# 02_56V-24V.net
KiCad netlist of a schematic drawn in Altium Designer
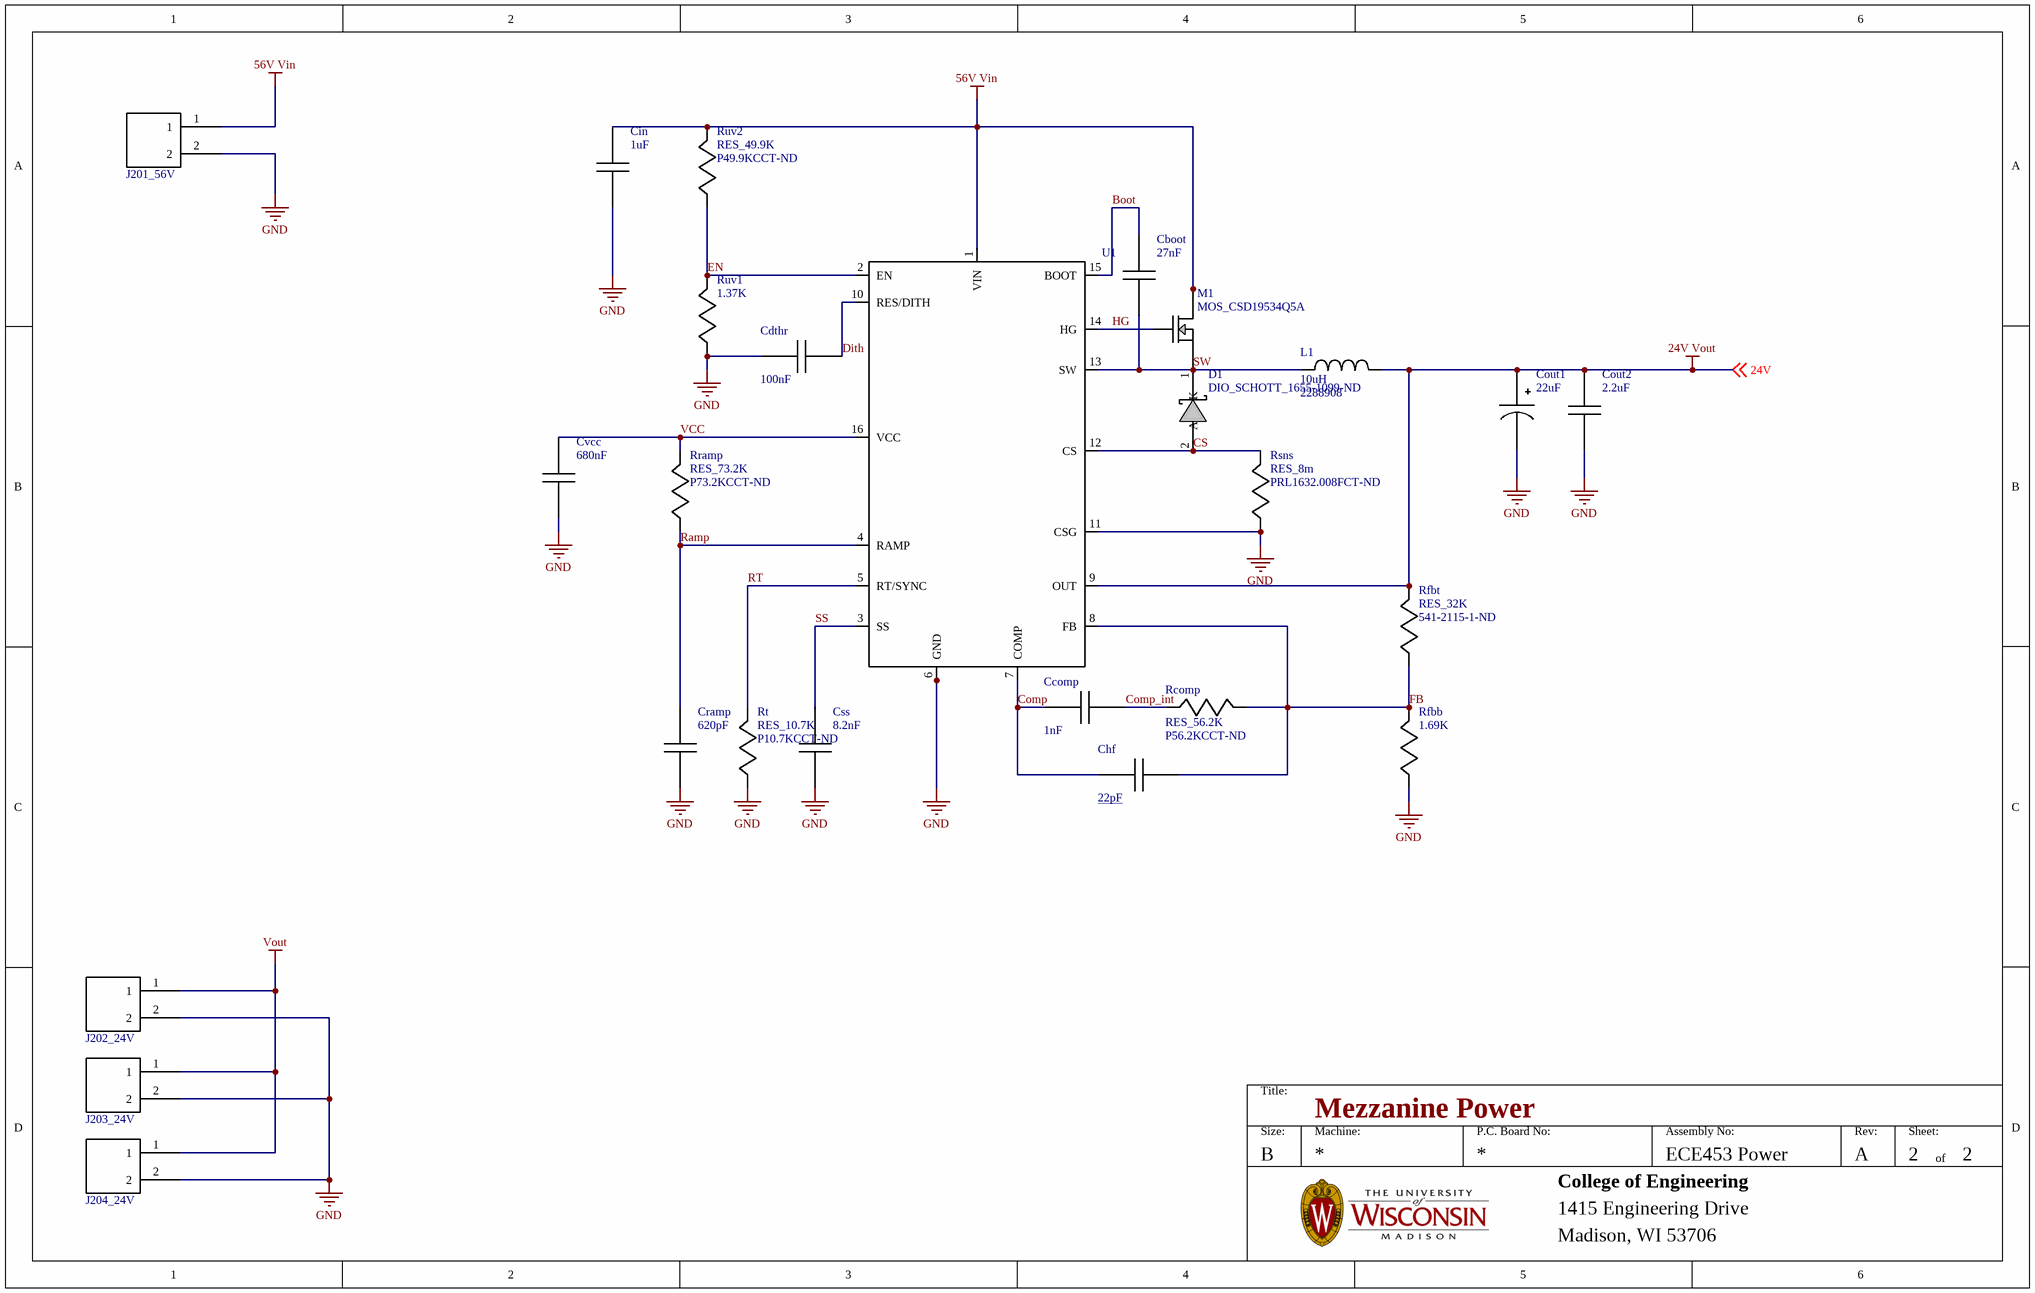
[diagram p0: 02 56V-24V.SchDoc]

(export (version "E")
  (design (tool "Eeschema 10.0.6"))
  (components
    (comp (ref "Cboot")
      (value "CAP_27nF")
      (footprint "CAP_1812")
      (description "Imported")
      (fields
        (field (name "MANUFACTURER_PART_NUMBER") "C1812C273J5GACTU")
        (field (name "MANUFACTURER") "KEMET")
        (field (name "CAPACITANCE") "27nF")
      )
      (libsource (lib "ECE453_PWR") (part "CAP_27nF"))
    )
    (comp (ref "Ccomp")
      (value "CAP_1nF")
      (footprint "CAP_0805")
      (description "Imported")
      (fields
        (field (name "MANUFACTURER_PART_NUMBER") "C0805C102K5GACTU")
        (field (name "MANUFACTURER") "KEMET")
        (field (name "CAPACITANCE") "1nF")
      )
      (libsource (lib "ECE453_PWR") (part "CAP_1nF"))
    )
    (comp (ref "Cdthr")
      (value "CAP_100nF")
      (footprint "CAP_0805")
      (description "Imported")
      (fields
        (field (name "MANUFACTURER_PART_NUMBER") "08053C104JAZ2A")
        (field (name "MANUFACTURER") "AVX Corporation")
        (field (name "CAPACITANCE") "100nF")
      )
      (libsource (lib "ECE453_PWR") (part "CAP_100nF"))
    )
    (comp (ref "Chf")
      (value "CAP_22pF")
      (footprint "CAP_0805")
      (description "Imported")
      (fields
        (field (name "MANUFACTURER_PART_NUMBER") "C0805C220K3GACTU")
        (field (name "MANUFACTURER") "KEMET")
        (field (name "CAPACITANCE") "22pF")
      )
      (libsource (lib "ECE453_PWR") (part "CAP_22pF"))
    )
    (comp (ref "Cin")
      (value "CAP_1uF")
      (footprint "CAP_1207")
      (description "Imported")
      (fields
        (field (name "MANUFACTURER_PART_NUMBER") "C3216X7R2A105K160AA")
        (field (name "MANUFACTURER") "TDK Corporation")
        (field (name "CAPACITANCE") "1uF")
      )
      (libsource (lib "ECE453_PWR") (part "CAP_1uF"))
    )
    (comp (ref "Cout1")
      (value "PCAP_22uF")
      (footprint "CAP_RAD_35SVPF22M")
      (description "Imported")
      (fields
        (field (name "MANUFACTURER_PART_NUMBER") "35SVPF22M")
        (field (name "MANUFACTURER") "Panasonic Electronic Components")
        (field (name "CAPACITANCE") "22uF")
      )
      (libsource (lib "ECE453_PWR") (part "PCAP_22uF"))
    )
    (comp (ref "Cout2")
      (value "CAP_2.2uF")
      (footprint "CAP_0805")
      (description "Imported")
      (fields
        (field (name "MANUFACTURER_PART_NUMBER") "C2012X7R1H225K125AC")
        (field (name "MANUFACTURER") "TDK Corporation")
        (field (name "CAPACITANCE") "2.2uF")
      )
      (libsource (lib "ECE453_PWR") (part "CAP_2.2uF"))
    )
    (comp (ref "Cramp")
      (value "CAP_620pF")
      (footprint "CAP_0805")
      (description "Imported")
      (fields
        (field (name "MANUFACTURER_PART_NUMBER") "CL21C621JBCNNNC")
        (field (name "MANUFACTURER") "Samsung Electro-Mechanics")
        (field (name "CAPACITANCE") "620pF")
      )
      (libsource (lib "ECE453_PWR") (part "CAP_620pF"))
    )
    (comp (ref "Css")
      (value "CAP_8.2nF")
      (footprint "CAP_0805")
      (description "Imported")
      (fields
        (field (name "MANUFACTURER") "Murata Electronics North America")
        (field (name "MANUFACTURER PART NUMBER") "GRM2195C1H822JA01D")
        (field (name "CAPACITANCE") "8.2nF")
      )
      (libsource (lib "ECE453_PWR") (part "CAP_8.2nF"))
    )
    (comp (ref "Cvcc")
      (value "CAP_680nF")
      (footprint "CAP_1207")
      (description "Imported")
      (fields
        (field (name "MANUFACTURER_PART_NUMBER") "ECPU1C684MA5")
        (field (name "MANUFACTURER") "Panasonic Electronic Components")
        (field (name "CAPACITANCE") "680nF")
      )
      (libsource (lib "ECE453_PWR") (part "CAP_680nF"))
    )
    (comp (ref "D1")
      (value "DIO_SCHOTT_1655-1099-ND")
      (footprint "DIO_SCHOTT_MBRF10200")
      (description "Imported")
      (fields
        (field (name "MANUFACTURER") "SMC Diode Solutions")
        (field (name "MANUFACTURER PART NUMBER") "MBRF10200")
      )
      (libsource (lib "ECE453_PWR") (part "DIO_SCHOTT_1655-1099-ND"))
    )
    (comp (ref "J201_56V")
      (value "TERMINAL_SCREW_2x1")
      (footprint "TERM_2Pin")
      (description "TERM BLOCK PLUG 2POS STR 5.08MM")
      (fields
        (field (name "MANUFACTURER") "On Shore Technology Inc.")
        (field (name "MANUFACTURER PART NUMBER") "OSTTJ025153")
      )
      (libsource (lib "ECE453_PWR") (part "TERMINAL_SCREW_2x1"))
    )
    (comp (ref "J202_24V")
      (value "TERMINAL_SCREW_2x1")
      (footprint "TERM_2Pin")
      (description "TERM BLOCK PLUG 2POS STR 5.08MM")
      (fields
        (field (name "MANUFACTURER") "On Shore Technology Inc.")
        (field (name "MANUFACTURER PART NUMBER") "OSTTJ025153")
      )
      (libsource (lib "ECE453_PWR") (part "TERMINAL_SCREW_2x1"))
    )
    (comp (ref "J203_24V")
      (value "TERMINAL_SCREW_2x1")
      (footprint "TERM_2Pin")
      (description "TERM BLOCK PLUG 2POS STR 5.08MM")
      (fields
        (field (name "MANUFACTURER") "On Shore Technology Inc.")
        (field (name "MANUFACTURER PART NUMBER") "OSTTJ025153")
      )
      (libsource (lib "ECE453_PWR") (part "TERMINAL_SCREW_2x1"))
    )
    (comp (ref "J204_24V")
      (value "TERMINAL_SCREW_2x1")
      (footprint "TERM_2Pin")
      (description "TERM BLOCK PLUG 2POS STR 5.08MM")
      (fields
        (field (name "MANUFACTURER") "On Shore Technology Inc.")
        (field (name "MANUFACTURER PART NUMBER") "OSTTJ025153")
      )
      (libsource (lib "ECE453_PWR") (part "TERMINAL_SCREW_2x1"))
    )
    (comp (ref "L1")
      (value "IND_10uH")
      (footprint "IND_SER2900")
      (description "Imported")
      (fields
        (field (name "MANUFACTURER_PART_NUMBER") "SER2915L-103KL")
        (field (name "MANUFACTURER") "COILCRAFT")
        (field (name "INDUCTANCE") "10uH")
        (field (name "SUPPLIER PART NUMBER 1") "2288908")
      )
      (libsource (lib "ECE453_PWR") (part "IND_10uH"))
    )
    (comp (ref "M1")
      (value "MOS_CSD19534Q5A")
      (footprint "MOS_CSD19534Q5A")
      (description "Imported")
      (fields
        (field (name "MANUFACTURER_PART_NUMBER") "CSD19534Q5A")
        (field (name "MANUFACTURER") "Texas Instruments")
      )
      (libsource (lib "ECE453_PWR") (part "MOS_CSD19534Q5A"))
    )
    (comp (ref "Rcomp")
      (value "RES_56.2K")
      (footprint "RES_0805")
      (description "Imported")
      (fields
        (field (name "MANUFACTURER_PART_NUMBER") "ERJ-6ENF5622V")
        (field (name "MANUFACTURER") "Panasonic Electronic Components")
        (field (name "SUPPLIER PART NUMBER 1") "P56.2KCCT-ND")
      )
      (libsource (lib "ECE453_PWR") (part "RES_56.2K"))
    )
    (comp (ref "Rfbb")
      (value "RES_1.69K")
      (footprint "RES_0805")
      (description "Imported")
      (fields
        (field (name "MANUFACTURER_PART_NUMBER") "ERJ-6ENF1691V")
        (field (name "MANUFACTURER") "Panasonic Electronic Components")
        (field (name "RESISTANCE") "1.69K")
      )
      (libsource (lib "ECE453_PWR") (part "RES_1.69K"))
    )
    (comp (ref "Rfbt")
      (value "RES_32K")
      (footprint "RES_0402")
      (description "Imported")
      (fields
        (field (name "MANUFACTURER") "Vishay Dale")
        (field (name "MANUFACTURER PART NUMBER") "TNPW040232K0BEED")
        (field (name "SUPPLIER PART NUMBER 1") "541-2115-1-ND")
      )
      (libsource (lib "ECE453_PWR") (part "RES_32K"))
    )
    (comp (ref "Rramp")
      (value "RES_73.2K")
      (footprint "RES_0805")
      (description "Imported")
      (fields
        (field (name "MANUFACTURER_PART_NUMBER") "ERJ-6ENF7322V")
        (field (name "MANUFACTURER") "Panasonic Electronic Components")
        (field (name "SUPPLIER PART NUMBER 1") "P73.2KCCT-ND")
      )
      (libsource (lib "ECE453_PWR") (part "RES_73.2K"))
    )
    (comp (ref "Rsns")
      (value "RES_8m")
      (footprint "RES_1206")
      (description "Imported")
      (fields
        (field (name "MANUFACTURER_PART_NUMBER") "PRL1632-R008-F-T1")
        (field (name "MANUFACTURER") "Susumu")
        (field (name "SUPPLIER PART NUMBER 1") "PRL1632.008FCT-ND")
      )
      (libsource (lib "ECE453_PWR") (part "RES_8m"))
    )
    (comp (ref "Rt")
      (value "RES_10.7K")
      (footprint "RES_0805")
      (description "Imported")
      (fields
        (field (name "MANUFACTURER_PART_NUMBER") "ERJ-6ENF1072V")
        (field (name "MANUFACTURER") "Panasonic Electronic Components")
        (field (name "SUPPLIER PART NUMBER 1") "P10.7KCCT-ND")
      )
      (libsource (lib "ECE453_PWR") (part "RES_10.7K"))
    )
    (comp (ref "Ruv1")
      (value "RES_1.37K")
      (footprint "RES_0805")
      (description "Imported")
      (fields
        (field (name "MANUFACTURER_PART_NUMBER") "CRCW08051K37FKEA")
        (field (name "MANUFACTURER") "Vishay Dale")
        (field (name "RESISTANCE") "1.37K")
      )
      (libsource (lib "ECE453_PWR") (part "RES_1.37K"))
    )
    (comp (ref "Ruv2")
      (value "RES_49.9K")
      (footprint "RES_0805")
      (description "Imported")
      (fields
        (field (name "MANUFACTURER_PART_NUMBER") "ERJ-6ENF4992V")
        (field (name "MANUFACTURER") "Panasonic Electronic Components")
        (field (name "SUPPLIER PART NUMBER 1") "P49.9KCCT-ND")
      )
      (libsource (lib "ECE453_PWR") (part "RES_49.9K"))
    )
    (comp (ref "U1")
      (value "BUCK_LM5088QMHX-1/NOP")
      (footprint "BUCK_LM5088")
      (description "Imported")
      (fields
        (field (name "MANUFACTURER_PART_NUMBER") "LM5088MHX-2/NOPB")
        (field (name "MANUFACTURER") "Texas Instruments")
      )
      (libsource (lib "ECE453_PWR") (part "BUCK_LM5088QMHX-1/NOP"))
    )
  )
  (nets
    (net (code "1") (name "/Boot") (class "Default")
      (node (ref "Cboot") (pin "1") (pinfunction "1_1") (pintype "passive"))
      (node (ref "U1") (pin "15") (pinfunction "BOOT_15") (pintype "passive"))
    )
    (net (code "2") (name "/CS") (class "Default")
      (node (ref "D1") (pin "2") (pinfunction "A_2") (pintype "passive"))
      (node (ref "Rsns") (pin "1") (pinfunction "1_1") (pintype "passive"))
      (node (ref "U1") (pin "12") (pinfunction "CS_12") (pintype "passive"))
    )
    (net (code "3") (name "/Comp") (class "Default")
      (node (ref "Ccomp") (pin "2") (pinfunction "2_2") (pintype "passive"))
      (node (ref "Chf") (pin "2") (pinfunction "2_2") (pintype "passive"))
      (node (ref "U1") (pin "7") (pinfunction "COMP_7") (pintype "passive"))
    )
    (net (code "4") (name "/Comp_int") (class "Default")
      (node (ref "Ccomp") (pin "1") (pinfunction "1_1") (pintype "passive"))
      (node (ref "Rcomp") (pin "2") (pinfunction "2_2") (pintype "passive"))
    )
    (net (code "5") (name "/Dith") (class "Default")
      (node (ref "Cdthr") (pin "1") (pinfunction "1_1") (pintype "passive"))
      (node (ref "U1") (pin "10") (pinfunction "RES/DITH_10") (pintype "passive"))
    )
    (net (code "6") (name "/EN") (class "Default")
      (node (ref "Ruv1") (pin "1") (pinfunction "1_1") (pintype "passive"))
      (node (ref "Ruv2") (pin "2") (pinfunction "2_2") (pintype "passive"))
      (node (ref "U1") (pin "2") (pinfunction "EN_2") (pintype "passive"))
    )
    (net (code "7") (name "/FB") (class "Default")
      (node (ref "Chf") (pin "1") (pinfunction "1_1") (pintype "passive"))
      (node (ref "Rcomp") (pin "1") (pinfunction "1_1") (pintype "passive"))
      (node (ref "Rfbb") (pin "1") (pinfunction "1_1") (pintype "passive"))
      (node (ref "Rfbt") (pin "2") (pinfunction "2_2") (pintype "passive"))
      (node (ref "U1") (pin "8") (pinfunction "FB_8") (pintype "passive"))
    )
    (net (code "8") (name "/HG") (class "Default")
      (node (ref "M1") (pin "4") (pinfunction "Gate_4") (pintype "passive"))
      (node (ref "U1") (pin "14") (pinfunction "HG_14") (pintype "passive"))
    )
    (net (code "9") (name "/RT") (class "Default")
      (node (ref "Rt") (pin "1") (pinfunction "1_1") (pintype "passive"))
      (node (ref "U1") (pin "5") (pinfunction "RT/SYNC_5") (pintype "passive"))
    )
    (net (code "10") (name "/Ramp") (class "Default")
      (node (ref "Cramp") (pin "1") (pinfunction "1_1") (pintype "passive"))
      (node (ref "Rramp") (pin "2") (pinfunction "2_2") (pintype "passive"))
      (node (ref "U1") (pin "4") (pinfunction "RAMP_4") (pintype "passive"))
    )
    (net (code "11") (name "/SS") (class "Default")
      (node (ref "Css") (pin "1") (pinfunction "1_1") (pintype "passive"))
      (node (ref "U1") (pin "3") (pinfunction "SS_3") (pintype "passive"))
    )
    (net (code "12") (name "/SW") (class "Default")
      (node (ref "Cboot") (pin "2") (pinfunction "2_2") (pintype "passive"))
      (node (ref "D1") (pin "1") (pinfunction "K_1") (pintype "passive"))
      (node (ref "L1") (pin "1") (pinfunction "1_1") (pintype "passive"))
      (node (ref "M1") (pin "1") (pinfunction "Source_1") (pintype "passive"))
      (node (ref "M1") (pin "2") (pinfunction "Source_2") (pintype "passive"))
      (node (ref "M1") (pin "3") (pinfunction "Source_3") (pintype "passive"))
      (node (ref "U1") (pin "13") (pinfunction "SW_13") (pintype "passive"))
    )
    (net (code "13") (name "/VCC") (class "Default")
      (node (ref "Cvcc") (pin "1") (pinfunction "1_1") (pintype "passive"))
      (node (ref "Rramp") (pin "1") (pinfunction "1_1") (pintype "passive"))
      (node (ref "U1") (pin "16") (pinfunction "VCC_16") (pintype "passive"))
    )
    (net (code "14") (name "24V") (class "Default")
      (node (ref "Cout1") (pin "1") (pinfunction "+_1") (pintype "passive"))
      (node (ref "Cout2") (pin "1") (pinfunction "1_1") (pintype "passive"))
      (node (ref "L1") (pin "2") (pinfunction "2_2") (pintype "passive"))
      (node (ref "Rfbt") (pin "1") (pinfunction "1_1") (pintype "passive"))
      (node (ref "U1") (pin "9") (pinfunction "OUT_9") (pintype "passive"))
    )
    (net (code "15") (name "56V Vin") (class "Default")
      (node (ref "Cin") (pin "1") (pinfunction "1_1") (pintype "passive"))
      (node (ref "J201_56V") (pin "1") (pinfunction "1_1") (pintype "passive"))
      (node (ref "M1") (pin "5") (pinfunction "Drain_5") (pintype "passive"))
      (node (ref "M1") (pin "6") (pinfunction "Drain_6") (pintype "passive"))
      (node (ref "M1") (pin "7") (pinfunction "Drain_7") (pintype "passive"))
      (node (ref "M1") (pin "8") (pinfunction "Drain_8") (pintype "passive"))
      (node (ref "Ruv2") (pin "1") (pinfunction "1_1") (pintype "passive"))
      (node (ref "U1") (pin "1") (pinfunction "VIN_1") (pintype "power_in"))
    )
    (net (code "16") (name "GND") (class "Default")
      (node (ref "Cdthr") (pin "2") (pinfunction "2_2") (pintype "passive"))
      (node (ref "Cin") (pin "2") (pinfunction "2_2") (pintype "passive"))
      (node (ref "Cout1") (pin "2") (pinfunction "-_2") (pintype "passive"))
      (node (ref "Cout2") (pin "2") (pinfunction "2_2") (pintype "passive"))
      (node (ref "Cramp") (pin "2") (pinfunction "2_2") (pintype "passive"))
      (node (ref "Css") (pin "2") (pinfunction "2_2") (pintype "passive"))
      (node (ref "Cvcc") (pin "2") (pinfunction "2_2") (pintype "passive"))
      (node (ref "J201_56V") (pin "2") (pinfunction "2_2") (pintype "passive"))
      (node (ref "J202_24V") (pin "2") (pinfunction "2_2") (pintype "passive"))
      (node (ref "J203_24V") (pin "2") (pinfunction "2_2") (pintype "passive"))
      (node (ref "J204_24V") (pin "2") (pinfunction "2_2") (pintype "passive"))
      (node (ref "Rfbb") (pin "2") (pinfunction "2_2") (pintype "passive"))
      (node (ref "Rsns") (pin "2") (pinfunction "2_2") (pintype "passive"))
      (node (ref "Rt") (pin "2") (pinfunction "2_2") (pintype "passive"))
      (node (ref "Ruv1") (pin "2") (pinfunction "2_2") (pintype "passive"))
      (node (ref "U1") (pin "11") (pinfunction "CSG_11") (pintype "passive"))
      (node (ref "U1") (pin "17") (pinfunction "EP_17") (pintype "passive"))
      (node (ref "U1") (pin "6") (pinfunction "GND_6") (pintype "power_in"))
    )
    (net (code "17") (name "Vout") (class "Default")
      (node (ref "J202_24V") (pin "1") (pinfunction "1_1") (pintype "passive"))
      (node (ref "J203_24V") (pin "1") (pinfunction "1_1") (pintype "passive"))
      (node (ref "J204_24V") (pin "1") (pinfunction "1_1") (pintype "passive"))
    )
  )
)
